# 3V-Switcher-50mA.net
KiCad netlist of a schematic drawn in Altium Designer
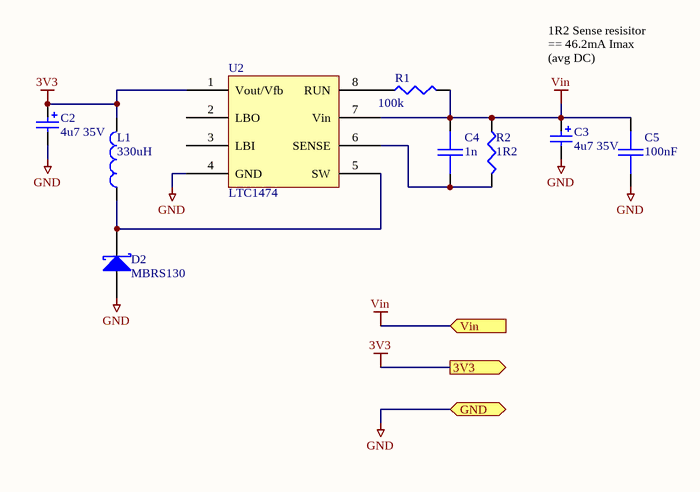
[diagram p0: 3V-Switcher-50mA.SchDoc]

(export (version "E")
  (design (tool "Eeschema 10.0.6"))
  (components
    (comp (ref "C2")
      (value "4u7 35V")
      (footprint "MCCT-CASEC")
      (description "Polarized Capacitor (Surface Mount)")
      (libsource (lib "Miscellaneous Devices") (part "Cap Pol3"))
    )
    (comp (ref "C3")
      (value "4u7 35V")
      (footprint "MCCT-CASEC")
      (description "Polarized Capacitor (Surface Mount)")
      (libsource (lib "Miscellaneous Devices") (part "Cap Pol3"))
    )
    (comp (ref "C4")
      (value "1n")
      (footprint "0603")
      (description "Capacitor")
      (libsource (lib "Miscellaneous Devices") (part "CAP"))
    )
    (comp (ref "C5")
      (value "100nF")
      (footprint "0603")
      (description "Capacitor")
      (libsource (lib "Miscellaneous Devices") (part "CAP"))
    )
    (comp (ref "D2")
      (value "MBRS130")
      (footprint "SMB")
      (description "Schottky Diode")
      (libsource (lib "RCLDQ") (part "D SCHOTTKY"))
    )
    (comp (ref "L1")
      (value "330uH")
      (footprint "1812")
      (description "Inductor")
      (libsource (lib "Miscellaneous Devices") (part "Inductor"))
    )
    (comp (ref "R1")
      (value "100k")
      (footprint "0603")
      (description "Resistor")
      (libsource (lib "RCLDQ") (part "RES1"))
    )
    (comp (ref "R2")
      (value "1R2")
      (footprint "0603")
      (description "Resistor")
      (libsource (lib "Miscellaneous Devices") (part "RES1"))
    )
    (comp (ref "U2")
      (value "LTC1474")
      (footprint "SO8")
      (description "Step-down converter")
      (libsource (lib "MiscellaneousIC") (part "LTC1474"))
    )
  )
  (nets
    (net (code "1") (name "3V3") (class "Default")
      (node (ref "C2") (pin "1") (pinfunction "1_1") (pintype "passive"))
      (node (ref "L1") (pin "2") (pinfunction "2_2") (pintype "passive"))
      (node (ref "U2") (pin "1") (pinfunction "Vout/Vfb_1") (pintype "passive"))
    )
    (net (code "2") (name "GND") (class "Default")
      (node (ref "C2") (pin "2") (pinfunction "2_2") (pintype "passive"))
      (node (ref "C3") (pin "2") (pinfunction "2_2") (pintype "passive"))
      (node (ref "C5") (pin "2") (pinfunction "2_2") (pintype "passive"))
      (node (ref "D2") (pin "A") (pinfunction "A_A") (pintype "passive"))
      (node (ref "U2") (pin "4") (pinfunction "GND_4") (pintype "passive"))
    )
    (net (code "3") (name "Net-(U2-RUN)") (class "Default")
      (node (ref "R1") (pin "1") (pinfunction "1_1") (pintype "passive"))
      (node (ref "U2") (pin "8") (pinfunction "RUN_8") (pintype "passive"))
    )
    (net (code "4") (name "Net-(U2-SENSE)") (class "Default")
      (node (ref "C4") (pin "2") (pinfunction "2_2") (pintype "passive"))
      (node (ref "R2") (pin "2") (pinfunction "2_2") (pintype "passive"))
      (node (ref "U2") (pin "6") (pinfunction "SENSE_6") (pintype "passive"))
    )
    (net (code "5") (name "Net-(U2-SW)") (class "Default")
      (node (ref "D2") (pin "K") (pinfunction "K_K") (pintype "passive"))
      (node (ref "L1") (pin "1") (pinfunction "1_1") (pintype "passive"))
      (node (ref "U2") (pin "5") (pinfunction "SW_5") (pintype "passive"))
    )
    (net (code "6") (name "Vin") (class "Default")
      (node (ref "C3") (pin "1") (pinfunction "1_1") (pintype "passive"))
      (node (ref "C4") (pin "1") (pinfunction "1_1") (pintype "passive"))
      (node (ref "C5") (pin "1") (pinfunction "1_1") (pintype "passive"))
      (node (ref "R1") (pin "2") (pinfunction "2_2") (pintype "passive"))
      (node (ref "R2") (pin "1") (pinfunction "1_1") (pintype "passive"))
      (node (ref "U2") (pin "7") (pinfunction "Vin_7") (pintype "passive"))
    )
    (net (code "7") (name "unconnected-(U2-LBI-Pad3)") (class "Default")
      (node (ref "U2") (pin "3") (pinfunction "LBI_3") (pintype "passive"))
    )
    (net (code "8") (name "unconnected-(U2-LBO-Pad2)") (class "Default")
      (node (ref "U2") (pin "2") (pinfunction "LBO_2") (pintype "passive"))
    )
  )
)
